# Top.net
KiCad netlist of a schematic drawn in Altium Designer
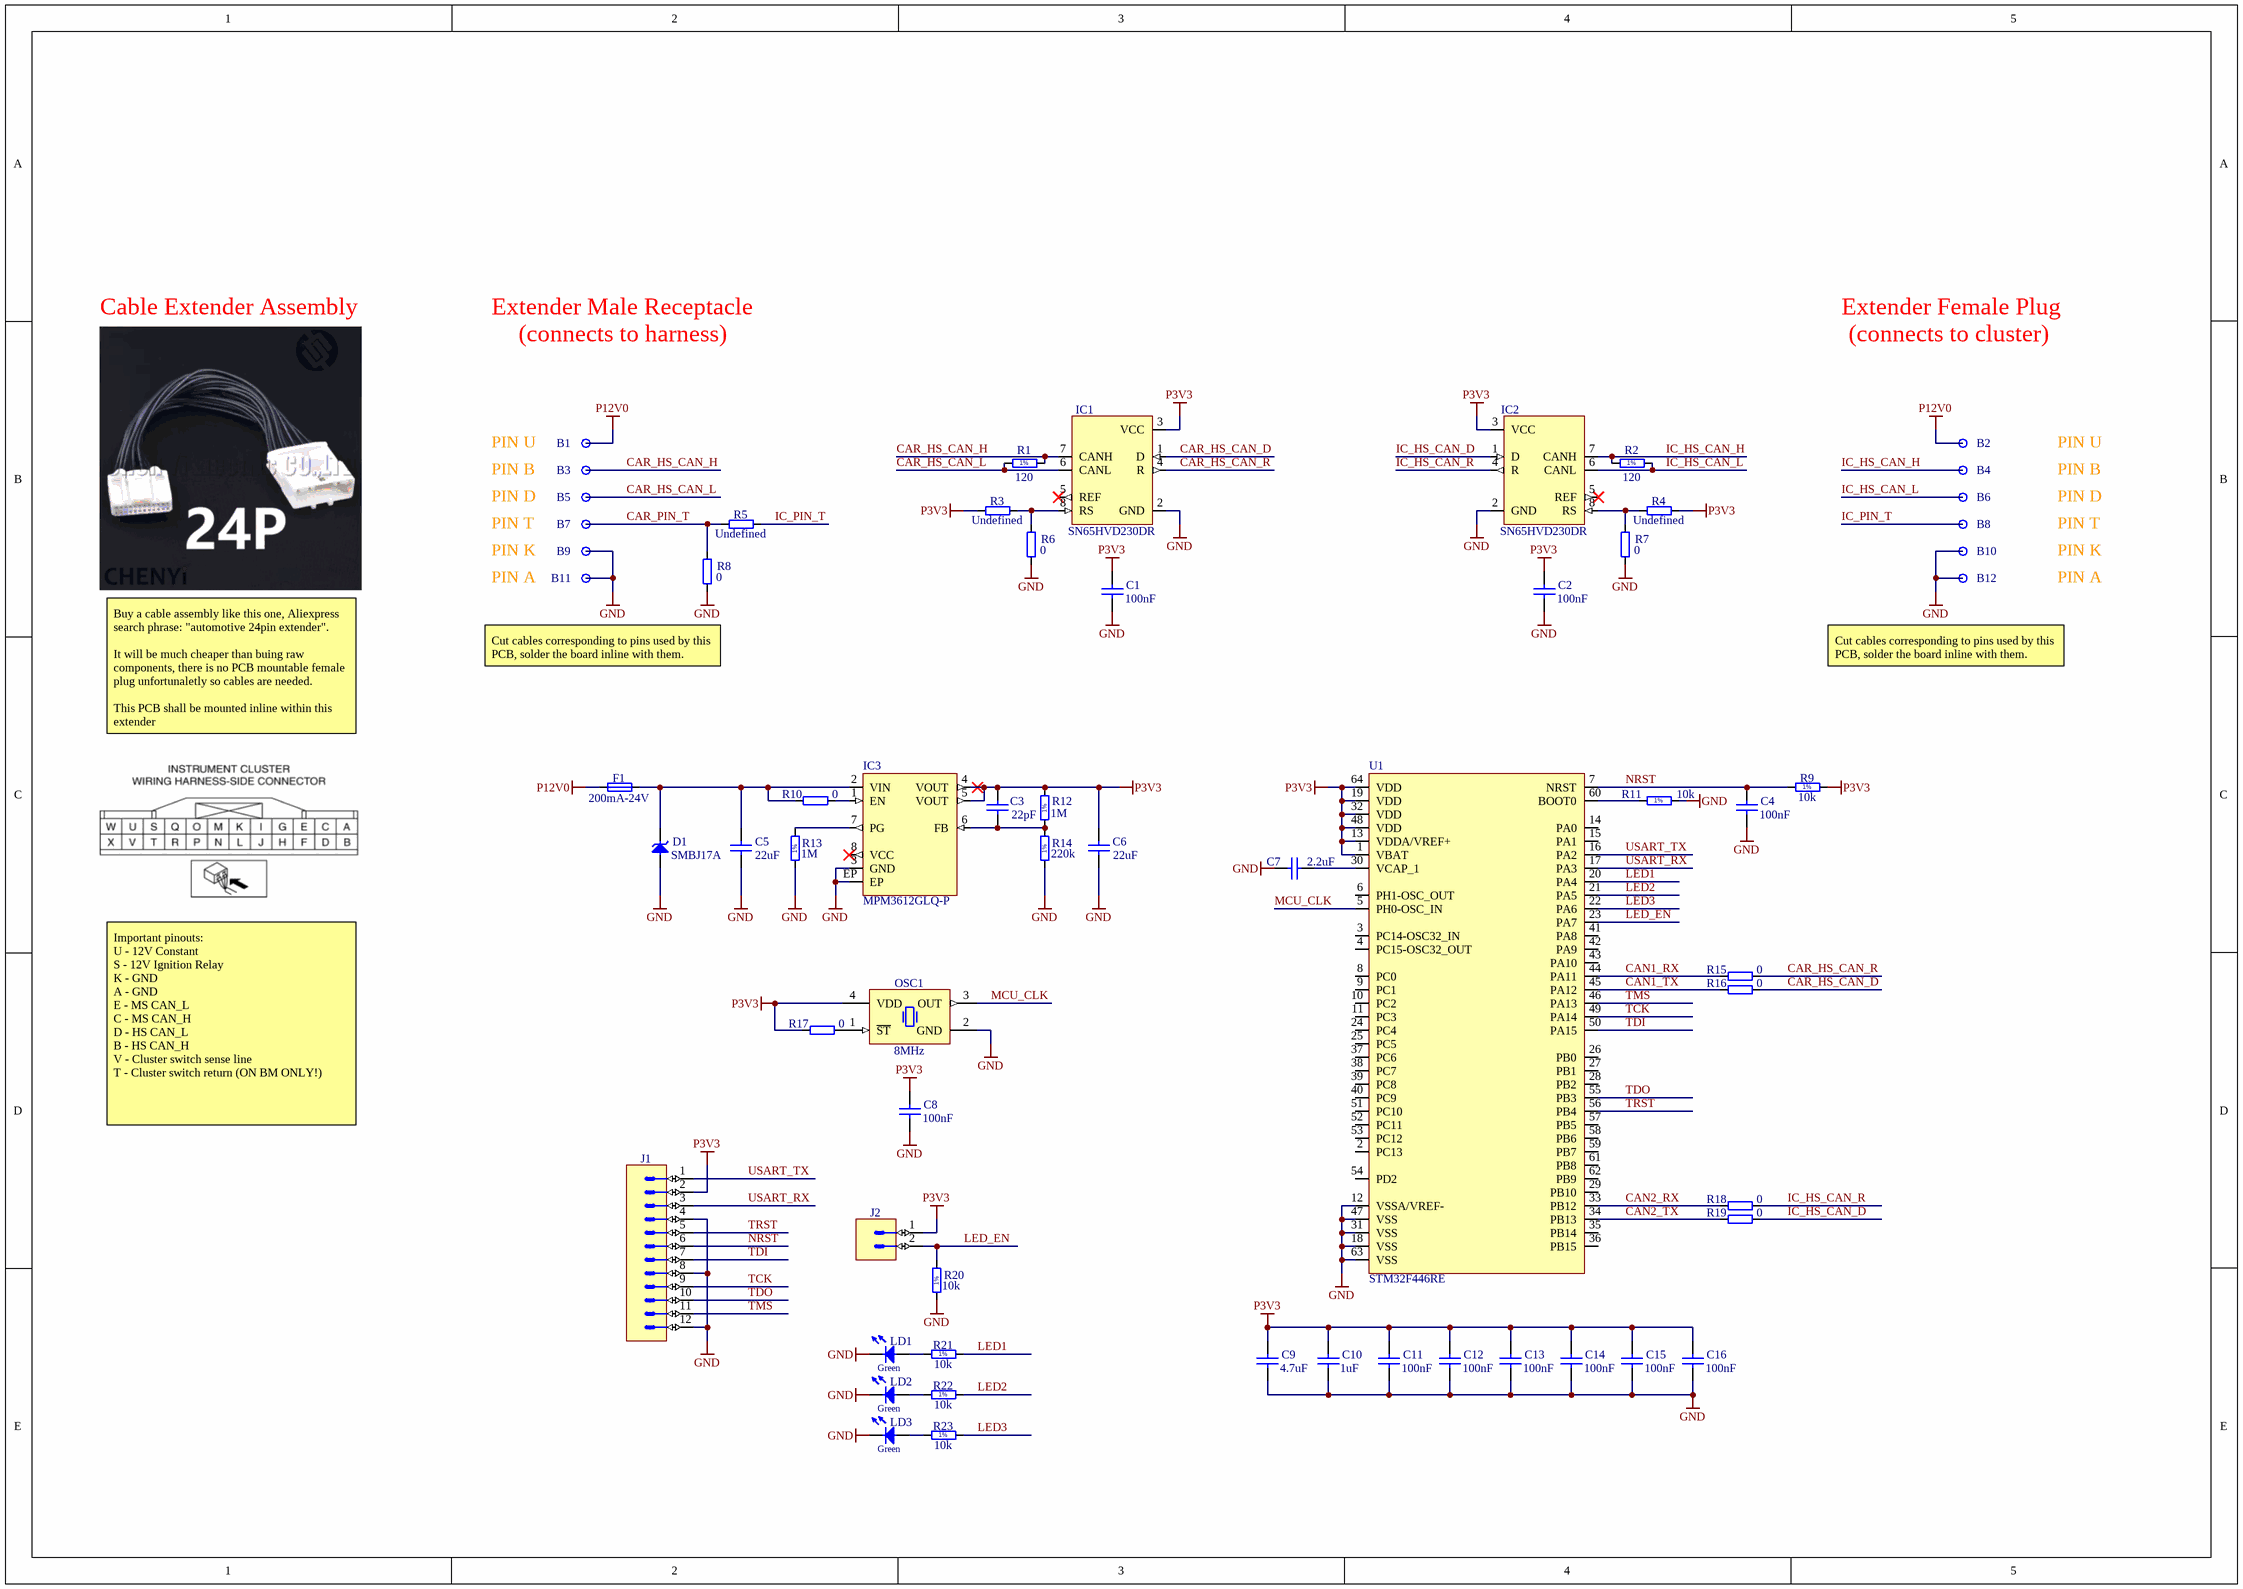
[diagram p0: Top.SchDoc]

(export (version "E")
  (design (tool "Eeschema 10.0.6"))
  (components
    (comp (ref "B1")
      (value "Plated Hole")
      (footprint "c170h100")
      (description "Single Terminal Socket")
      (fields (field (name "PART NUMBER") "PLATED_HOLE1.0_PAD1.7") (field (name "AUTHOR") "CERN DEM JLC"))
      (libsource (lib "Eletro-mechanical") (part "Single Terminal Socket"))
    )
    (comp (ref "B2")
      (value "Plated Hole")
      (footprint "c170h100")
      (description "Single Terminal Socket")
      (fields (field (name "PART NUMBER") "PLATED_HOLE1.0_PAD1.7") (field (name "AUTHOR") "CERN DEM JLC"))
      (libsource (lib "Eletro-mechanical") (part "Single Terminal Socket"))
    )
    (comp (ref "B3")
      (value "Plated Hole")
      (footprint "c170h100")
      (description "Single Terminal Socket")
      (fields (field (name "PART NUMBER") "PLATED_HOLE1.0_PAD1.7") (field (name "AUTHOR") "CERN DEM JLC"))
      (libsource (lib "Eletro-mechanical") (part "Single Terminal Socket"))
    )
    (comp (ref "B4")
      (value "Plated Hole")
      (footprint "c170h100")
      (description "Single Terminal Socket")
      (fields (field (name "PART NUMBER") "PLATED_HOLE1.0_PAD1.7") (field (name "AUTHOR") "CERN DEM JLC"))
      (libsource (lib "Eletro-mechanical") (part "Single Terminal Socket"))
    )
    (comp (ref "B5")
      (value "Plated Hole")
      (footprint "c170h100")
      (description "Single Terminal Socket")
      (fields (field (name "PART NUMBER") "PLATED_HOLE1.0_PAD1.7") (field (name "AUTHOR") "CERN DEM JLC"))
      (libsource (lib "Eletro-mechanical") (part "Single Terminal Socket"))
    )
    (comp (ref "B6")
      (value "Plated Hole")
      (footprint "c170h100")
      (description "Single Terminal Socket")
      (fields (field (name "PART NUMBER") "PLATED_HOLE1.0_PAD1.7") (field (name "AUTHOR") "CERN DEM JLC"))
      (libsource (lib "Eletro-mechanical") (part "Single Terminal Socket"))
    )
    (comp (ref "B7")
      (value "Plated Hole")
      (footprint "c170h100")
      (description "Single Terminal Socket")
      (fields (field (name "PART NUMBER") "PLATED_HOLE1.0_PAD1.7") (field (name "AUTHOR") "CERN DEM JLC"))
      (libsource (lib "Eletro-mechanical") (part "Single Terminal Socket"))
    )
    (comp (ref "B8")
      (value "Plated Hole")
      (footprint "c170h100")
      (description "Single Terminal Socket")
      (fields (field (name "PART NUMBER") "PLATED_HOLE1.0_PAD1.7") (field (name "AUTHOR") "CERN DEM JLC"))
      (libsource (lib "Eletro-mechanical") (part "Single Terminal Socket"))
    )
    (comp (ref "B9")
      (value "Plated Hole")
      (footprint "c170h100")
      (description "Single Terminal Socket")
      (fields (field (name "PART NUMBER") "PLATED_HOLE1.0_PAD1.7") (field (name "AUTHOR") "CERN DEM JLC"))
      (libsource (lib "Eletro-mechanical") (part "Single Terminal Socket"))
    )
    (comp (ref "B10")
      (value "Plated Hole")
      (footprint "c170h100")
      (description "Single Terminal Socket")
      (fields (field (name "PART NUMBER") "PLATED_HOLE1.0_PAD1.7") (field (name "AUTHOR") "CERN DEM JLC"))
      (libsource (lib "Eletro-mechanical") (part "Single Terminal Socket"))
    )
    (comp (ref "B11")
      (value "Plated Hole")
      (footprint "c170h100")
      (description "Single Terminal Socket")
      (fields (field (name "PART NUMBER") "PLATED_HOLE1.0_PAD1.7") (field (name "AUTHOR") "CERN DEM JLC"))
      (libsource (lib "Eletro-mechanical") (part "Single Terminal Socket"))
    )
    (comp (ref "B12")
      (value "Plated Hole")
      (footprint "c170h100")
      (description "Single Terminal Socket")
      (fields (field (name "PART NUMBER") "PLATED_HOLE1.0_PAD1.7") (field (name "AUTHOR") "CERN DEM JLC"))
      (libsource (lib "Eletro-mechanical") (part "Single Terminal Socket"))
    )
    (comp (ref "C1")
      (value "100nF")
      (footprint "CAPC1608X87N")
      (description "Non-polarised capacitor")
      (fields
        (field (name "PART NUMBER") "CC0603_100NF_50V_10%_X5R")
        (field (name "VOLTAGE") "50V")
        (field (name "AUTHOR") "CERN DEM MR")
      )
      (libsource (lib "Capacitors") (part "Capacitor - non polarized"))
    )
    (comp (ref "C2")
      (value "100nF")
      (footprint "CAPC1608X87N")
      (description "Non-polarised capacitor")
      (fields
        (field (name "PART NUMBER") "CC0603_100NF_50V_10%_X5R")
        (field (name "VOLTAGE") "50V")
        (field (name "AUTHOR") "CERN DEM MR")
      )
      (libsource (lib "Capacitors") (part "Capacitor - non polarized"))
    )
    (comp (ref "C3")
      (value "22pF")
      (footprint "CAPC1608X87N")
      (description "Non-polarised capacitor")
      (fields
        (field (name "PART NUMBER") "CC0603_22PF_50V_5%_NP0")
        (field (name "VOLTAGE") "50V")
        (field (name "AUTHOR") "CERN DEM JLC")
      )
      (libsource (lib "Capacitors") (part "Capacitor - non polarized"))
    )
    (comp (ref "C4")
      (value "100nF")
      (footprint "CAPC1608X87N")
      (description "Non-polarised capacitor")
      (fields
        (field (name "PART NUMBER") "CC0603_100NF_50V_10%_X5R")
        (field (name "VOLTAGE") "50V")
        (field (name "AUTHOR") "CERN DEM MR")
      )
      (libsource (lib "Capacitors") (part "Capacitor - non polarized"))
    )
    (comp (ref "C5")
      (value "22uF")
      (footprint "CAPC2012X135N")
      (description "Non-polarised capacitor")
      (fields
        (field (name "PART NUMBER") "CC0805_22UF_25V_20%_X6S")
        (field (name "VOLTAGE") "25V")
        (field (name "AUTHOR") "CERN DEM JLC")
      )
      (libsource (lib "Capacitors") (part "Capacitor - non polarized"))
    )
    (comp (ref "C6")
      (value "22uF")
      (footprint "CAPC2012X135N")
      (description "Non-polarised capacitor")
      (fields
        (field (name "PART NUMBER") "CC0805_22UF_25V_20%_X6S")
        (field (name "VOLTAGE") "25V")
        (field (name "AUTHOR") "CERN DEM JLC")
      )
      (libsource (lib "Capacitors") (part "Capacitor - non polarized"))
    )
    (comp (ref "C7")
      (value "2.2uF")
      (footprint "CAPC1608X90N")
      (description "Non-polarised capacitor")
      (fields
        (field (name "PART NUMBER") "CC0603_2.2UF_10V_20%_X7R")
        (field (name "VOLTAGE") "10V")
        (field (name "AUTHOR") "CERN DEM JLC")
      )
      (libsource (lib "Capacitors") (part "Capacitor - non polarized"))
    )
    (comp (ref "C8")
      (value "100nF")
      (footprint "CAPC1608X87N")
      (description "Non-polarised capacitor")
      (fields
        (field (name "PART NUMBER") "CC0603_100NF_50V_10%_X5R")
        (field (name "VOLTAGE") "50V")
        (field (name "AUTHOR") "CERN DEM MR")
      )
      (libsource (lib "Capacitors") (part "Capacitor - non polarized"))
    )
    (comp (ref "C9")
      (value "4.7uF")
      (footprint "CAPC1608X87N")
      (description "Non-polarised capacitor")
      (fields
        (field (name "PART NUMBER") "CC0603_4.7UF_6.3V_10%_X5R")
        (field (name "VOLTAGE") "6.3V")
        (field (name "AUTHOR") "CERN DEM JLC")
      )
      (libsource (lib "Capacitors") (part "Capacitor - non polarized"))
    )
    (comp (ref "C10")
      (value "1uF")
      (footprint "CAPC1608X87N")
      (description "Non-polarised capacitor")
      (fields
        (field (name "PART NUMBER") "CC0603_1UF_16V_10%_X7R")
        (field (name "VOLTAGE") "16V")
        (field (name "AUTHOR") "CERN DEM JLC")
      )
      (libsource (lib "Capacitors") (part "Capacitor - non polarized"))
    )
    (comp (ref "C11")
      (value "100nF")
      (footprint "CAPC1608X87N")
      (description "Non-polarised capacitor")
      (fields
        (field (name "PART NUMBER") "CC0603_100NF_50V_10%_X5R")
        (field (name "VOLTAGE") "50V")
        (field (name "AUTHOR") "CERN DEM MR")
      )
      (libsource (lib "Capacitors") (part "Capacitor - non polarized"))
    )
    (comp (ref "C12")
      (value "100nF")
      (footprint "CAPC1608X87N")
      (description "Non-polarised capacitor")
      (fields
        (field (name "PART NUMBER") "CC0603_100NF_50V_10%_X5R")
        (field (name "VOLTAGE") "50V")
        (field (name "AUTHOR") "CERN DEM MR")
      )
      (libsource (lib "Capacitors") (part "Capacitor - non polarized"))
    )
    (comp (ref "C13")
      (value "100nF")
      (footprint "CAPC1608X87N")
      (description "Non-polarised capacitor")
      (fields
        (field (name "PART NUMBER") "CC0603_100NF_50V_10%_X5R")
        (field (name "VOLTAGE") "50V")
        (field (name "AUTHOR") "CERN DEM MR")
      )
      (libsource (lib "Capacitors") (part "Capacitor - non polarized"))
    )
    (comp (ref "C14")
      (value "100nF")
      (footprint "CAPC1608X87N")
      (description "Non-polarised capacitor")
      (fields
        (field (name "PART NUMBER") "CC0603_100NF_50V_10%_X5R")
        (field (name "VOLTAGE") "50V")
        (field (name "AUTHOR") "CERN DEM MR")
      )
      (libsource (lib "Capacitors") (part "Capacitor - non polarized"))
    )
    (comp (ref "C15")
      (value "100nF")
      (footprint "CAPC1608X87N")
      (description "Non-polarised capacitor")
      (fields
        (field (name "PART NUMBER") "CC0603_100NF_50V_10%_X5R")
        (field (name "VOLTAGE") "50V")
        (field (name "AUTHOR") "CERN DEM MR")
      )
      (libsource (lib "Capacitors") (part "Capacitor - non polarized"))
    )
    (comp (ref "C16")
      (value "100nF")
      (footprint "CAPC1608X87N")
      (description "Non-polarised capacitor")
      (fields
        (field (name "PART NUMBER") "CC0603_100NF_50V_10%_X5R")
        (field (name "VOLTAGE") "50V")
        (field (name "AUTHOR") "CERN DEM MR")
      )
      (libsource (lib "Capacitors") (part "Capacitor - non polarized"))
    )
    (comp (ref "D1")
      (value "SMBJ17A")
      (footprint "DIOM5336X265N")
      (description "Zener Diode")
      (fields
        (field (name "VOLTAGE") "17V")
        (field (name "POWER") "600W")
        (field (name "AUTHOR") "CERN DEM JLC")
      )
      (libsource (lib "ICs And Semiconductors") (part "Diode Zener"))
    )
    (comp (ref "F1")
      (value "200mA-24V")
      (footprint "FUSR_LITTELFUSE_0805L010")
      (description "Fuse")
      (fields (field (name "PART NUMBER") "0805L020/24YR") (field (name "AUTHOR") "CERN DEM JLC"))
      (libsource (lib "Eletro-mechanical") (part "Fuse"))
    )
    (comp (ref "IC1")
      (value "SN65HVD230DR")
      (footprint "SOIC127P600X175-8N")
      (description "3.3V CAN Bus Transceiver")
      (fields (field (name "AUTHOR") "CERN DEM JMW"))
      (libsource (lib "Lib") (part "SN65HVD230DR"))
    )
    (comp (ref "IC2")
      (value "SN65HVD230DR")
      (footprint "SOIC127P600X175-8N")
      (description "3.3V CAN Bus Transceiver")
      (fields (field (name "AUTHOR") "CERN DEM JMW"))
      (libsource (lib "") (part "SN65HVD230DR_1"))
    )
    (comp (ref "IC3")
      (value "MPM3612GLQ-P")
      (footprint "LGA10")
      (libsource (lib "Lib") (part "MPM3612GLQ-P"))
    )
    (comp (ref "J1")
      (value "Header 12")
      (footprint "SAMTEC_TSW-106-23-L-D")
      (description "Connector 12 Male")
      (fields
        (field (name "PART NUMBER") "SAMTEC_TSW-106-23-L-D")
        (field (name "MANUFACTURER1 PART NUMBER") "TSW-106-23-L-D")
        (field (name "AUTHOR") "CERN DEM MR")
      )
      (libsource (lib "Connectors") (part "Connector 12 Male"))
    )
    (comp (ref "J2")
      (value "Header 2")
      (footprint "SAMTEC_TSW-101-23-L-D")
      (description "Connector 2 Male")
      (fields
        (field (name "PART NUMBER") "SAMTEC_TSW-101-23-L-D")
        (field (name "MANUFACTURER1 PART NUMBER") "TSW-101-23-L-D")
        (field (name "AUTHOR") "CERN DEM MR")
      )
      (libsource (lib "Connectors") (part "Connector 2 Male"))
    )
    (comp (ref "LD1")
      (value "Green")
      (footprint "LED_KINGBRIGHT_KPH-1608CGCK")
      (description "LED Green 1C 2A")
      (fields
        (field (name "PART NUMBER") "LED_KINGBRIGHT_KPH-1608CGCK")
        (field (name "MANUFACTURER1 PART NUMBER") "KPH-1608CGCK")
        (field (name "AUTHOR") "CERN DEM JLC")
      )
      (libsource (lib "ICs And Semiconductors") (part "LED Green 1C 2A"))
    )
    (comp (ref "LD2")
      (value "Green")
      (footprint "LED_KINGBRIGHT_KPH-1608CGCK")
      (description "LED Green 1C 2A")
      (fields
        (field (name "PART NUMBER") "LED_KINGBRIGHT_KPH-1608CGCK")
        (field (name "MANUFACTURER1 PART NUMBER") "KPH-1608CGCK")
        (field (name "AUTHOR") "CERN DEM JLC")
      )
      (libsource (lib "ICs And Semiconductors") (part "LED Green 1C 2A"))
    )
    (comp (ref "LD3")
      (value "Green")
      (footprint "LED_KINGBRIGHT_KPH-1608CGCK")
      (description "LED Green 1C 2A")
      (fields
        (field (name "PART NUMBER") "LED_KINGBRIGHT_KPH-1608CGCK")
        (field (name "MANUFACTURER1 PART NUMBER") "KPH-1608CGCK")
        (field (name "AUTHOR") "CERN DEM JLC")
      )
      (libsource (lib "ICs And Semiconductors") (part "LED Green 1C 2A"))
    )
    (comp (ref "OSC1")
      (value "8MHz")
      (footprint "OSC_MICROCHIP_CDFN2520-4LD-PL-1")
      (description "Oscillator 4 pins 1=S\\T\\ 2=GND 3=OUT 4=VDD")
      (fields
        (field (name "PART NUMBER") "OSC_8MHZ_MICROCHIP_DSC1003DL2-008.0000")
        (field (name "MANUFACTURER1 PART NUMBER") "DSC1003DL2-008.0000")
        (field (name "AUTHOR") "CERN DEM JLC")
      )
      (libsource (lib "ICs And Semiconductors") (part "Oscillator 1S{backslash}T{backslash} 2GND 3OUT 4VDD"))
    )
    (comp (ref "R1")
      (value "120")
      (footprint "RESC3216X65N")
      (description "Resistor - 1%")
      (fields
        (field (name "PART NUMBER") "R1206_120R_1%_0.25W_100PPM")
        (field (name "POWER") "0.25W")
        (field (name "AUTHOR") "CERN DEM JLC")
      )
      (libsource (lib "Resistors") (part "Resistor - 1%"))
    )
    (comp (ref "R2")
      (value "120")
      (footprint "RESC3216X65N")
      (description "Resistor - 1%")
      (fields
        (field (name "PART NUMBER") "R1206_120R_1%_0.25W_100PPM")
        (field (name "POWER") "0.25W")
        (field (name "AUTHOR") "CERN DEM JLC")
      )
      (libsource (lib "Resistors") (part "Resistor - 1%"))
    )
    (comp (ref "R3")
      (value "Undefined")
      (footprint "RESC1608X55N")
      (description "Resistor")
      (fields (field (name "PART NUMBER") "R0603_NO-VALUE") (field (name "AUTHOR") "CERN DEM JLC"))
      (libsource (lib "Resistors") (part "Resistor"))
    )
    (comp (ref "R4")
      (value "Undefined")
      (footprint "RESC1608X55N")
      (description "Resistor")
      (fields (field (name "PART NUMBER") "R0603_NO-VALUE") (field (name "AUTHOR") "CERN DEM JLC"))
      (libsource (lib "Resistors") (part "Resistor"))
    )
    (comp (ref "R5")
      (value "Undefined")
      (footprint "RESC1608X55N")
      (description "Resistor")
      (fields (field (name "PART NUMBER") "R0603_NO-VALUE") (field (name "AUTHOR") "CERN DEM JLC"))
      (libsource (lib "Resistors") (part "Resistor"))
    )
    (comp (ref "R6")
      (value "0")
      (footprint "RESC1608X55N")
      (description "Resistor")
      (fields
        (field (name "PART NUMBER") "R0603_0R_JUMPER")
        (field (name "MANUFACTURER") "GENERIC")
        (field (name "AUTHOR") "CERN DEM JLC")
      )
      (libsource (lib "Resistors") (part "Resistor"))
    )
    (comp (ref "R7")
      (value "0")
      (footprint "RESC1608X55N")
      (description "Resistor")
      (fields
        (field (name "PART NUMBER") "R0603_0R_JUMPER")
        (field (name "MANUFACTURER") "GENERIC")
        (field (name "AUTHOR") "CERN DEM JLC")
      )
      (libsource (lib "Resistors") (part "Resistor"))
    )
    (comp (ref "R8")
      (value "0")
      (footprint "RESC1608X55N")
      (description "Resistor")
      (fields
        (field (name "PART NUMBER") "R0603_0R_JUMPER")
        (field (name "MANUFACTURER") "GENERIC")
        (field (name "AUTHOR") "CERN DEM JLC")
      )
      (libsource (lib "Resistors") (part "Resistor"))
    )
    (comp (ref "R9")
      (value "10k")
      (footprint "RESC1608X55N")
      (description "Resistor - 1%")
      (fields
        (field (name "PART NUMBER") "R0603_10K_1%_0.1W_100PPM")
        (field (name "POWER") "0.1W")
        (field (name "AUTHOR") "CERN DEM JLC")
      )
      (libsource (lib "Resistors") (part "Resistor - 1%"))
    )
    (comp (ref "R10")
      (value "0")
      (footprint "RESC1608X55N")
      (description "Resistor")
      (fields
        (field (name "PART NUMBER") "R0603_0R_JUMPER")
        (field (name "MANUFACTURER") "GENERIC")
        (field (name "AUTHOR") "CERN DEM JLC")
      )
      (libsource (lib "Resistors") (part "Resistor"))
    )
    (comp (ref "R11")
      (value "10k")
      (footprint "RESC1608X55N")
      (description "Resistor - 1%")
      (fields
        (field (name "PART NUMBER") "R0603_10K_1%_0.1W_100PPM")
        (field (name "POWER") "0.1W")
        (field (name "AUTHOR") "CERN DEM JLC")
      )
      (libsource (lib "Resistors") (part "Resistor - 1%"))
    )
    (comp (ref "R12")
      (value "1M")
      (footprint "RESC1608X55N")
      (description "Resistor - 1%")
      (fields
        (field (name "PART NUMBER") "R0603_1M_1%_0.1W_100PPM")
        (field (name "POWER") "0.1W")
        (field (name "AUTHOR") "CERN DEM JLC")
      )
      (libsource (lib "Resistors") (part "Resistor - 1%"))
    )
    (comp (ref "R13")
      (value "1M")
      (footprint "RESC1608X55N")
      (description "Resistor - 1%")
      (fields
        (field (name "PART NUMBER") "R0603_1M_1%_0.1W_100PPM")
        (field (name "POWER") "0.1W")
        (field (name "AUTHOR") "CERN DEM JLC")
      )
      (libsource (lib "Resistors") (part "Resistor - 1%"))
    )
    (comp (ref "R14")
      (value "220k")
      (footprint "RESC1608X55N")
      (description "Resistor - 1%")
      (fields
        (field (name "PART NUMBER") "R0603_220K_1%_0.1W_100PPM")
        (field (name "POWER") "0.1W")
        (field (name "AUTHOR") "CERN DEM JLC")
      )
      (libsource (lib "Resistors") (part "Resistor - 1%"))
    )
    (comp (ref "R15")
      (value "0")
      (footprint "RESC1608X55N")
      (description "Resistor")
      (fields
        (field (name "PART NUMBER") "R0603_0R_JUMPER")
        (field (name "MANUFACTURER") "GENERIC")
        (field (name "AUTHOR") "CERN DEM JLC")
      )
      (libsource (lib "Resistors") (part "Resistor"))
    )
    (comp (ref "R16")
      (value "0")
      (footprint "RESC1608X55N")
      (description "Resistor")
      (fields
        (field (name "PART NUMBER") "R0603_0R_JUMPER")
        (field (name "MANUFACTURER") "GENERIC")
        (field (name "AUTHOR") "CERN DEM JLC")
      )
      (libsource (lib "Resistors") (part "Resistor"))
    )
    (comp (ref "R17")
      (value "0")
      (footprint "RESC1608X55N")
      (description "Resistor")
      (fields
        (field (name "PART NUMBER") "R0603_0R_JUMPER")
        (field (name "MANUFACTURER") "GENERIC")
        (field (name "AUTHOR") "CERN DEM JLC")
      )
      (libsource (lib "Resistors") (part "Resistor"))
    )
    (comp (ref "R18")
      (value "0")
      (footprint "RESC1608X55N")
      (description "Resistor")
      (fields
        (field (name "PART NUMBER") "R0603_0R_JUMPER")
        (field (name "MANUFACTURER") "GENERIC")
        (field (name "AUTHOR") "CERN DEM JLC")
      )
      (libsource (lib "Resistors") (part "Resistor"))
    )
    (comp (ref "R19")
      (value "0")
      (footprint "RESC1608X55N")
      (description "Resistor")
      (fields
        (field (name "PART NUMBER") "R0603_0R_JUMPER")
        (field (name "MANUFACTURER") "GENERIC")
        (field (name "AUTHOR") "CERN DEM JLC")
      )
      (libsource (lib "Resistors") (part "Resistor"))
    )
    (comp (ref "R20")
      (value "10k")
      (footprint "RESC1608X55N")
      (description "Resistor - 1%")
      (fields
        (field (name "PART NUMBER") "R0603_10K_1%_0.1W_100PPM")
        (field (name "POWER") "0.1W")
        (field (name "AUTHOR") "CERN DEM JLC")
      )
      (libsource (lib "Resistors") (part "Resistor - 1%"))
    )
    (comp (ref "R21")
      (value "10k")
      (footprint "RESC1608X55N")
      (description "Resistor - 1%")
      (fields
        (field (name "PART NUMBER") "R0603_10K_1%_0.1W_100PPM")
        (field (name "POWER") "0.1W")
        (field (name "AUTHOR") "CERN DEM JLC")
      )
      (libsource (lib "Resistors") (part "Resistor - 1%"))
    )
    (comp (ref "R22")
      (value "10k")
      (footprint "RESC1608X55N")
      (description "Resistor - 1%")
      (fields
        (field (name "PART NUMBER") "R0603_10K_1%_0.1W_100PPM")
        (field (name "POWER") "0.1W")
        (field (name "AUTHOR") "CERN DEM JLC")
      )
      (libsource (lib "Resistors") (part "Resistor - 1%"))
    )
    (comp (ref "R23")
      (value "10k")
      (footprint "RESC1608X55N")
      (description "Resistor - 1%")
      (fields
        (field (name "PART NUMBER") "R0603_10K_1%_0.1W_100PPM")
        (field (name "POWER") "0.1W")
        (field (name "AUTHOR") "CERN DEM JLC")
      )
      (libsource (lib "Resistors") (part "Resistor - 1%"))
    )
    (comp (ref "U1")
      (value "STM32F446RE")
      (footprint "STM-LQFP64_N")
      (description "Arm® Cortex®-M4 core with DSP and FPU, 512 Kbytes Flash, 180 MHz CPU, ART Accelerator, Dual QSPI")
      (fields (field (name "MANUFACTURER1 PART NUMBER") "STM32F446RET7") (field (name "AUTHOR") "PC"))
      (libsource (lib "ICs And Semiconductors") (part "STM32F446RE"))
    )
  )
  (nets
    (net (code "1") (name "/CAN1_RX") (class "Default")
      (node (ref "R15") (pin "2") (pinfunction "2_2") (pintype "passive"))
      (node (ref "U1") (pin "44") (pinfunction "PA11_44") (pintype "passive"))
    )
    (net (code "2") (name "/CAN1_TX") (class "Default")
      (node (ref "R16") (pin "2") (pinfunction "2_2") (pintype "passive"))
      (node (ref "U1") (pin "45") (pinfunction "PA12_45") (pintype "passive"))
    )
    (net (code "3") (name "/CAN2_RX") (class "Default")
      (node (ref "R18") (pin "2") (pinfunction "2_2") (pintype "passive"))
      (node (ref "U1") (pin "33") (pinfunction "PB12_33") (pintype "passive"))
    )
    (net (code "4") (name "/CAN2_TX") (class "Default")
      (node (ref "R19") (pin "2") (pinfunction "2_2") (pintype "passive"))
      (node (ref "U1") (pin "34") (pinfunction "PB13_34") (pintype "passive"))
    )
    (net (code "5") (name "/CAR_HS_CAN_D") (class "Default")
      (node (ref "IC1") (pin "1") (pinfunction "D_1") (pintype "input"))
      (node (ref "R16") (pin "1") (pinfunction "1_1") (pintype "passive"))
    )
    (net (code "6") (name "/CAR_HS_CAN_H") (class "Default")
      (node (ref "B3") (pin "1") (pinfunction "1_1") (pintype "bidirectional"))
      (node (ref "IC1") (pin "7") (pinfunction "CANH_7") (pintype "bidirectional"))
      (node (ref "R1") (pin "1") (pinfunction "1_1") (pintype "passive"))
    )
    (net (code "7") (name "/CAR_HS_CAN_L") (class "Default")
      (node (ref "B5") (pin "1") (pinfunction "1_1") (pintype "bidirectional"))
      (node (ref "IC1") (pin "6") (pinfunction "CANL_6") (pintype "bidirectional"))
      (node (ref "R1") (pin "2") (pinfunction "2_2") (pintype "passive"))
    )
    (net (code "8") (name "/CAR_HS_CAN_R") (class "Default")
      (node (ref "IC1") (pin "4") (pinfunction "R_4") (pintype "output"))
      (node (ref "R15") (pin "1") (pinfunction "1_1") (pintype "passive"))
    )
    (net (code "9") (name "/CAR_PIN_T") (class "Default")
      (node (ref "B7") (pin "1") (pinfunction "1_1") (pintype "bidirectional"))
      (node (ref "R5") (pin "1") (pinfunction "1_1") (pintype "passive"))
      (node (ref "R8") (pin "2") (pinfunction "2_2") (pintype "passive"))
    )
    (net (code "10") (name "/IC_HS_CAN_D") (class "Default")
      (node (ref "IC2") (pin "1") (pinfunction "D_1") (pintype "input"))
      (node (ref "R19") (pin "1") (pinfunction "1_1") (pintype "passive"))
    )
    (net (code "11") (name "/IC_HS_CAN_H") (class "Default")
      (node (ref "B4") (pin "1") (pinfunction "1_1") (pintype "bidirectional"))
      (node (ref "IC2") (pin "7") (pinfunction "CANH_7") (pintype "bidirectional"))
      (node (ref "R2") (pin "1") (pinfunction "1_1") (pintype "passive"))
    )
    (net (code "12") (name "/IC_HS_CAN_L") (class "Default")
      (node (ref "B6") (pin "1") (pinfunction "1_1") (pintype "bidirectional"))
      (node (ref "IC2") (pin "6") (pinfunction "CANL_6") (pintype "bidirectional"))
      (node (ref "R2") (pin "2") (pinfunction "2_2") (pintype "passive"))
    )
    (net (code "13") (name "/IC_HS_CAN_R") (class "Default")
      (node (ref "IC2") (pin "4") (pinfunction "R_4") (pintype "output"))
      (node (ref "R18") (pin "1") (pinfunction "1_1") (pintype "passive"))
    )
    (net (code "14") (name "/IC_PIN_T") (class "Default")
      (node (ref "B8") (pin "1") (pinfunction "1_1") (pintype "bidirectional"))
      (node (ref "R5") (pin "2") (pinfunction "2_2") (pintype "passive"))
    )
    (net (code "15") (name "/LED1") (class "Default")
      (node (ref "R21") (pin "2") (pinfunction "2_2") (pintype "passive"))
      (node (ref "U1") (pin "20") (pinfunction "PA4_20") (pintype "passive"))
    )
    (net (code "16") (name "/LED2") (class "Default")
      (node (ref "R22") (pin "2") (pinfunction "2_2") (pintype "passive"))
      (node (ref "U1") (pin "21") (pinfunction "PA5_21") (pintype "passive"))
    )
    (net (code "17") (name "/LED3") (class "Default")
      (node (ref "R23") (pin "2") (pinfunction "2_2") (pintype "passive"))
      (node (ref "U1") (pin "22") (pinfunction "PA6_22") (pintype "passive"))
    )
    (net (code "18") (name "/LED_EN") (class "Default")
      (node (ref "J2") (pin "2") (pinfunction "2_2") (pintype "bidirectional"))
      (node (ref "R20") (pin "2") (pinfunction "2_2") (pintype "passive"))
      (node (ref "U1") (pin "23") (pinfunction "PA7_23") (pintype "passive"))
    )
    (net (code "19") (name "/MCU_CLK") (class "Default")
      (node (ref "OSC1") (pin "3") (pinfunction "OUT_3") (pintype "output"))
      (node (ref "U1") (pin "5") (pinfunction "PH0-OSC_IN_5") (pintype "passive"))
    )
    (net (code "20") (name "/NRST") (class "Default")
      (node (ref "C4") (pin "2") (pinfunction "2_2") (pintype "passive"))
      (node (ref "J1") (pin "6") (pinfunction "6_6") (pintype "bidirectional"))
      (node (ref "R9") (pin "1") (pinfunction "1_1") (pintype "passive"))
      (node (ref "U1") (pin "7") (pinfunction "NRST_7") (pintype "passive"))
    )
    (net (code "21") (name "/TCK") (class "Default")
      (node (ref "J1") (pin "9") (pinfunction "9_9") (pintype "bidirectional"))
      (node (ref "U1") (pin "49") (pinfunction "PA14_49") (pintype "passive"))
    )
    (net (code "22") (name "/TDI") (class "Default")
      (node (ref "J1") (pin "7") (pinfunction "7_7") (pintype "bidirectional"))
      (node (ref "U1") (pin "50") (pinfunction "PA15_50") (pintype "passive"))
    )
    (net (code "23") (name "/TDO") (class "Default")
      (node (ref "J1") (pin "10") (pinfunction "10_10") (pintype "bidirectional"))
      (node (ref "U1") (pin "55") (pinfunction "PB3_55") (pintype "passive"))
    )
    (net (code "24") (name "/TMS") (class "Default")
      (node (ref "J1") (pin "11") (pinfunction "11_11") (pintype "bidirectional"))
      (node (ref "U1") (pin "46") (pinfunction "PA13_46") (pintype "passive"))
    )
    (net (code "25") (name "/TRST") (class "Default")
      (node (ref "J1") (pin "5") (pinfunction "5_5") (pintype "bidirectional"))
      (node (ref "U1") (pin "56") (pinfunction "PB4_56") (pintype "passive"))
    )
    (net (code "26") (name "/USART_RX") (class "Default")
      (node (ref "J1") (pin "3") (pinfunction "3_3") (pintype "bidirectional"))
      (node (ref "U1") (pin "17") (pinfunction "PA3_17") (pintype "passive"))
    )
    (net (code "27") (name "/USART_TX") (class "Default")
      (node (ref "J1") (pin "1") (pinfunction "1_1") (pintype "bidirectional"))
      (node (ref "U1") (pin "16") (pinfunction "PA2_16") (pintype "passive"))
    )
    (net (code "28") (name "GND") (class "Default")
      (node (ref "B10") (pin "1") (pinfunction "1_1") (pintype "bidirectional"))
      (node (ref "B11") (pin "1") (pinfunction "1_1") (pintype "bidirectional"))
      (node (ref "B12") (pin "1") (pinfunction "1_1") (pintype "bidirectional"))
      (node (ref "B9") (pin "1") (pinfunction "1_1") (pintype "bidirectional"))
      (node (ref "C1") (pin "1") (pinfunction "1_1") (pintype "passive"))
      (node (ref "C10") (pin "1") (pinfunction "1_1") (pintype "passive"))
      (node (ref "C11") (pin "1") (pinfunction "1_1") (pintype "passive"))
      (node (ref "C12") (pin "1") (pinfunction "1_1") (pintype "passive"))
      (node (ref "C13") (pin "1") (pinfunction "1_1") (pintype "passive"))
      (node (ref "C14") (pin "1") (pinfunction "1_1") (pintype "passive"))
      (node (ref "C15") (pin "1") (pinfunction "1_1") (pintype "passive"))
      (node (ref "C16") (pin "1") (pinfunction "1_1") (pintype "passive"))
      (node (ref "C2") (pin "1") (pinfunction "1_1") (pintype "passive"))
      (node (ref "C4") (pin "1") (pinfunction "1_1") (pintype "passive"))
      (node (ref "C5") (pin "1") (pinfunction "1_1") (pintype "passive"))
      (node (ref "C6") (pin "1") (pinfunction "1_1") (pintype "passive"))
      (node (ref "C7") (pin "1") (pinfunction "1_1") (pintype "passive"))
      (node (ref "C8") (pin "1") (pinfunction "1_1") (pintype "passive"))
      (node (ref "C9") (pin "1") (pinfunction "1_1") (pintype "passive"))
      (node (ref "D1") (pin "2") (pinfunction "A_2") (pintype "passive"))
      (node (ref "IC1") (pin "2") (pinfunction "GND_2") (pintype "power_in"))
      (node (ref "IC2") (pin "2") (pinfunction "GND_2") (pintype "power_in"))
      (node (ref "IC3") (pin "3") (pinfunction "GND_3") (pintype "power_in"))
      (node (ref "IC3") (pin "EP") (pinfunction "EP_EP") (pintype "power_in"))
      (node (ref "J1") (pin "12") (pinfunction "12_12") (pintype "bidirectional"))
      (node (ref "J1") (pin "4") (pinfunction "4_4") (pintype "bidirectional"))
      (node (ref "J1") (pin "8") (pinfunction "8_8") (pintype "bidirectional"))
      (node (ref "LD1") (pin "1") (pinfunction "C_1") (pintype "passive"))
      (node (ref "LD2") (pin "1") (pinfunction "C_1") (pintype "passive"))
      (node (ref "LD3") (pin "1") (pinfunction "C_1") (pintype "passive"))
      (node (ref "OSC1") (pin "2") (pinfunction "GND_2") (pintype "power_in"))
      (node (ref "R11") (pin "2") (pinfunction "2_2") (pintype "passive"))
      (node (ref "R13") (pin "1") (pinfunction "1_1") (pintype "passive"))
      (node (ref "R14") (pin "1") (pinfunction "1_1") (pintype "passive"))
      (node (ref "R20") (pin "1") (pinfunction "1_1") (pintype "passive"))
      (node (ref "R6") (pin "1") (pinfunction "1_1") (pintype "passive"))
      (node (ref "R7") (pin "1") (pinfunction "1_1") (pintype "passive"))
      (node (ref "R8") (pin "1") (pinfunction "1_1") (pintype "passive"))
      (node (ref "U1") (pin "12") (pinfunction "VSSA/VREF-_12") (pintype "passive"))
      (node (ref "U1") (pin "18") (pinfunction "VSS_18") (pintype "passive"))
      (node (ref "U1") (pin "31") (pinfunction "VSS_31") (pintype "passive"))
      (node (ref "U1") (pin "47") (pinfunction "VSS_47") (pintype "passive"))
      (node (ref "U1") (pin "63") (pinfunction "VSS_63") (pintype "passive"))
    )
    (net (code "29") (name "Net-(D1-C)") (class "Default")
      (node (ref "C5") (pin "2") (pinfunction "2_2") (pintype "passive"))
      (node (ref "D1") (pin "1") (pinfunction "C_1") (pintype "passive"))
      (node (ref "F1") (pin "2") (pinfunction "2_2") (pintype "passive"))
      (node (ref "IC3") (pin "2") (pinfunction "VIN_2") (pintype "power_in"))
      (node (ref "R10") (pin "2") (pinfunction "2_2") (pintype "passive"))
    )
    (net (code "30") (name "Net-(IC1-RS)") (class "Default")
      (node (ref "IC1") (pin "8") (pinfunction "RS_8") (pintype "input"))
      (node (ref "R3") (pin "1") (pinfunction "1_1") (pintype "passive"))
      (node (ref "R6") (pin "2") (pinfunction "2_2") (pintype "passive"))
    )
    (net (code "31") (name "Net-(IC2-RS)") (class "Default")
      (node (ref "IC2") (pin "8") (pinfunction "RS_8") (pintype "input"))
      (node (ref "R4") (pin "1") (pinfunction "1_1") (pintype "passive"))
      (node (ref "R7") (pin "2") (pinfunction "2_2") (pintype "passive"))
    )
    (net (code "32") (name "Net-(IC3-EN)") (class "Default")
      (node (ref "IC3") (pin "1") (pinfunction "EN_1") (pintype "input"))
      (node (ref "R10") (pin "1") (pinfunction "1_1") (pintype "passive"))
    )
    (net (code "33") (name "Net-(IC3-FB)") (class "Default")
      (node (ref "C3") (pin "1") (pinfunction "1_1") (pintype "passive"))
      (node (ref "IC3") (pin "6") (pinfunction "FB_6") (pintype "input"))
      (node (ref "R12") (pin "1") (pinfunction "1_1") (pintype "passive"))
      (node (ref "R14") (pin "2") (pinfunction "2_2") (pintype "passive"))
    )
    (net (code "34") (name "Net-(IC3-PG)") (class "Default")
      (node (ref "IC3") (pin "7") (pinfunction "PG_7") (pintype "output"))
      (node (ref "R13") (pin "2") (pinfunction "2_2") (pintype "passive"))
    )
    (net (code "35") (name "Net-(LD1-A)") (class "Default")
      (node (ref "LD1") (pin "2") (pinfunction "A_2") (pintype "passive"))
      (node (ref "R21") (pin "1") (pinfunction "1_1") (pintype "passive"))
    )
    (net (code "36") (name "Net-(LD2-A)") (class "Default")
      (node (ref "LD2") (pin "2") (pinfunction "A_2") (pintype "passive"))
      (node (ref "R22") (pin "1") (pinfunction "1_1") (pintype "passive"))
    )
    (net (code "37") (name "Net-(LD3-A)") (class "Default")
      (node (ref "LD3") (pin "2") (pinfunction "A_2") (pintype "passive"))
      (node (ref "R23") (pin "1") (pinfunction "1_1") (pintype "passive"))
    )
    (net (code "38") (name "Net-(OSC1-~{ST})") (class "Default")
      (node (ref "OSC1") (pin "1") (pinfunction "~{ST}_1") (pintype "input"))
      (node (ref "R17") (pin "1") (pinfunction "1_1") (pintype "passive"))
    )
    (net (code "39") (name "Net-(U1-BOOT0)") (class "Default")
      (node (ref "R11") (pin "1") (pinfunction "1_1") (pintype "passive"))
      (node (ref "U1") (pin "60") (pinfunction "BOOT0_60") (pintype "passive"))
    )
    (net (code "40") (name "Net-(U1-VCAP_1)") (class "Default")
      (node (ref "C7") (pin "2") (pinfunction "2_2") (pintype "passive"))
      (node (ref "U1") (pin "30") (pinfunction "VCAP_1_30") (pintype "passive"))
    )
    (net (code "41") (name "P3V3") (class "Default")
      (node (ref "C1") (pin "2") (pinfunction "2_2") (pintype "passive"))
      (node (ref "C10") (pin "2") (pinfunction "2_2") (pintype "passive"))
      (node (ref "C11") (pin "2") (pinfunction "2_2") (pintype "passive"))
      (node (ref "C12") (pin "2") (pinfunction "2_2") (pintype "passive"))
      (node (ref "C13") (pin "2") (pinfunction "2_2") (pintype "passive"))
      (node (ref "C14") (pin "2") (pinfunction "2_2") (pintype "passive"))
      (node (ref "C15") (pin "2") (pinfunction "2_2") (pintype "passive"))
      (node (ref "C16") (pin "2") (pinfunction "2_2") (pintype "passive"))
      (node (ref "C2") (pin "2") (pinfunction "2_2") (pintype "passive"))
      (node (ref "C3") (pin "2") (pinfunction "2_2") (pintype "passive"))
      (node (ref "C6") (pin "2") (pinfunction "2_2") (pintype "passive"))
      (node (ref "C8") (pin "2") (pinfunction "2_2") (pintype "passive"))
      (node (ref "C9") (pin "2") (pinfunction "2_2") (pintype "passive"))
      (node (ref "IC1") (pin "3") (pinfunction "VCC_3") (pintype "power_in"))
      (node (ref "IC2") (pin "3") (pinfunction "VCC_3") (pintype "power_in"))
      (node (ref "IC3") (pin "4") (pinfunction "VOUT_4") (pintype "output"))
      (node (ref "IC3") (pin "5") (pinfunction "VOUT_5") (pintype "output"))
      (node (ref "J1") (pin "2") (pinfunction "2_2") (pintype "bidirectional"))
      (node (ref "J2") (pin "1") (pinfunction "1_1") (pintype "bidirectional"))
      (node (ref "OSC1") (pin "4") (pinfunction "VDD_4") (pintype "power_in"))
      (node (ref "R12") (pin "2") (pinfunction "2_2") (pintype "passive"))
      (node (ref "R17") (pin "2") (pinfunction "2_2") (pintype "passive"))
      (node (ref "R3") (pin "2") (pinfunction "2_2") (pintype "passive"))
      (node (ref "R4") (pin "2") (pinfunction "2_2") (pintype "passive"))
      (node (ref "R9") (pin "2") (pinfunction "2_2") (pintype "passive"))
      (node (ref "U1") (pin "1") (pinfunction "VBAT_1") (pintype "passive"))
      (node (ref "U1") (pin "13") (pinfunction "VDDA/VREF+_13") (pintype "passive"))
      (node (ref "U1") (pin "19") (pinfunction "VDD_19") (pintype "passive"))
      (node (ref "U1") (pin "32") (pinfunction "VDD_32") (pintype "passive"))
      (node (ref "U1") (pin "48") (pinfunction "VDD_48") (pintype "passive"))
      (node (ref "U1") (pin "64") (pinfunction "VDD_64") (pintype "passive"))
    )
    (net (code "42") (name "P12V0") (class "Default")
      (node (ref "B1") (pin "1") (pinfunction "1_1") (pintype "bidirectional"))
      (node (ref "B2") (pin "1") (pinfunction "1_1") (pintype "bidirectional"))
      (node (ref "F1") (pin "1") (pinfunction "1_1") (pintype "passive"))
    )
    (net (code "43") (name "unconnected-(IC1-REF-Pad5)") (class "Default")
      (node (ref "IC1") (pin "5") (pinfunction "REF_5") (pintype "output+no_connect"))
    )
    (net (code "44") (name "unconnected-(IC2-REF-Pad5)") (class "Default")
      (node (ref "IC2") (pin "5") (pinfunction "REF_5") (pintype "output+no_connect"))
    )
    (net (code "45") (name "unconnected-(IC3-VCC-Pad8)") (class "Default")
      (node (ref "IC3") (pin "8") (pinfunction "VCC_8") (pintype "output+no_connect"))
    )
    (net (code "46") (name "unconnected-(U1-PA0-Pad14)") (class "Default")
      (node (ref "U1") (pin "14") (pinfunction "PA0_14") (pintype "passive"))
    )
    (net (code "47") (name "unconnected-(U1-PA1-Pad15)") (class "Default")
      (node (ref "U1") (pin "15") (pinfunction "PA1_15") (pintype "passive"))
    )
    (net (code "48") (name "unconnected-(U1-PA8-Pad41)") (class "Default")
      (node (ref "U1") (pin "41") (pinfunction "PA8_41") (pintype "passive"))
    )
    (net (code "49") (name "unconnected-(U1-PA9-Pad42)") (class "Default")
      (node (ref "U1") (pin "42") (pinfunction "PA9_42") (pintype "passive"))
    )
    (net (code "50") (name "unconnected-(U1-PA10-Pad43)") (class "Default")
      (node (ref "U1") (pin "43") (pinfunction "PA10_43") (pintype "passive"))
    )
    (net (code "51") (name "unconnected-(U1-PB0-Pad26)") (class "Default")
      (node (ref "U1") (pin "26") (pinfunction "PB0_26") (pintype "passive"))
    )
    (net (code "52") (name "unconnected-(U1-PB1-Pad27)") (class "Default")
      (node (ref "U1") (pin "27") (pinfunction "PB1_27") (pintype "passive"))
    )
    (net (code "53") (name "unconnected-(U1-PB2-Pad28)") (class "Default")
      (node (ref "U1") (pin "28") (pinfunction "PB2_28") (pintype "passive"))
    )
    (net (code "54") (name "unconnected-(U1-PB5-Pad57)") (class "Default")
      (node (ref "U1") (pin "57") (pinfunction "PB5_57") (pintype "passive"))
    )
    (net (code "55") (name "unconnected-(U1-PB6-Pad58)") (class "Default")
      (node (ref "U1") (pin "58") (pinfunction "PB6_58") (pintype "passive"))
    )
    (net (code "56") (name "unconnected-(U1-PB7-Pad59)") (class "Default")
      (node (ref "U1") (pin "59") (pinfunction "PB7_59") (pintype "passive"))
    )
    (net (code "57") (name "unconnected-(U1-PB8-Pad61)") (class "Default")
      (node (ref "U1") (pin "61") (pinfunction "PB8_61") (pintype "passive"))
    )
    (net (code "58") (name "unconnected-(U1-PB9-Pad62)") (class "Default")
      (node (ref "U1") (pin "62") (pinfunction "PB9_62") (pintype "passive"))
    )
    (net (code "59") (name "unconnected-(U1-PB10-Pad29)") (class "Default")
      (node (ref "U1") (pin "29") (pinfunction "PB10_29") (pintype "passive"))
    )
    (net (code "60") (name "unconnected-(U1-PB14-Pad35)") (class "Default")
      (node (ref "U1") (pin "35") (pinfunction "PB14_35") (pintype "passive"))
    )
    (net (code "61") (name "unconnected-(U1-PB15-Pad36)") (class "Default")
      (node (ref "U1") (pin "36") (pinfunction "PB15_36") (pintype "passive"))
    )
    (net (code "62") (name "unconnected-(U1-PC0-Pad8)") (class "Default")
      (node (ref "U1") (pin "8") (pinfunction "PC0_8") (pintype "passive"))
    )
    (net (code "63") (name "unconnected-(U1-PC1-Pad9)") (class "Default")
      (node (ref "U1") (pin "9") (pinfunction "PC1_9") (pintype "passive"))
    )
    (net (code "64") (name "unconnected-(U1-PC2-Pad10)") (class "Default")
      (node (ref "U1") (pin "10") (pinfunction "PC2_10") (pintype "passive"))
    )
    (net (code "65") (name "unconnected-(U1-PC3-Pad11)") (class "Default")
      (node (ref "U1") (pin "11") (pinfunction "PC3_11") (pintype "passive"))
    )
    (net (code "66") (name "unconnected-(U1-PC4-Pad24)") (class "Default")
      (node (ref "U1") (pin "24") (pinfunction "PC4_24") (pintype "passive"))
    )
    (net (code "67") (name "unconnected-(U1-PC5-Pad25)") (class "Default")
      (node (ref "U1") (pin "25") (pinfunction "PC5_25") (pintype "passive"))
    )
    (net (code "68") (name "unconnected-(U1-PC6-Pad37)") (class "Default")
      (node (ref "U1") (pin "37") (pinfunction "PC6_37") (pintype "passive"))
    )
    (net (code "69") (name "unconnected-(U1-PC7-Pad38)") (class "Default")
      (node (ref "U1") (pin "38") (pinfunction "PC7_38") (pintype "passive"))
    )
    (net (code "70") (name "unconnected-(U1-PC8-Pad39)") (class "Default")
      (node (ref "U1") (pin "39") (pinfunction "PC8_39") (pintype "passive"))
    )
    (net (code "71") (name "unconnected-(U1-PC9-Pad40)") (class "Default")
      (node (ref "U1") (pin "40") (pinfunction "PC9_40") (pintype "passive"))
    )
    (net (code "72") (name "unconnected-(U1-PC10-Pad51)") (class "Default")
      (node (ref "U1") (pin "51") (pinfunction "PC10_51") (pintype "passive"))
    )
    (net (code "73") (name "unconnected-(U1-PC11-Pad52)") (class "Default")
      (node (ref "U1") (pin "52") (pinfunction "PC11_52") (pintype "passive"))
    )
    (net (code "74") (name "unconnected-(U1-PC12-Pad53)") (class "Default")
      (node (ref "U1") (pin "53") (pinfunction "PC12_53") (pintype "passive"))
    )
    (net (code "75") (name "unconnected-(U1-PC13-Pad2)") (class "Default")
      (node (ref "U1") (pin "2") (pinfunction "PC13_2") (pintype "passive"))
    )
    (net (code "76") (name "unconnected-(U1-PC14-OSC32_IN-Pad3)") (class "Default")
      (node (ref "U1") (pin "3") (pinfunction "PC14-OSC32_IN_3") (pintype "passive"))
    )
    (net (code "77") (name "unconnected-(U1-PC15-OSC32_OUT-Pad4)") (class "Default")
      (node (ref "U1") (pin "4") (pinfunction "PC15-OSC32_OUT_4") (pintype "passive"))
    )
    (net (code "78") (name "unconnected-(U1-PD2-Pad54)") (class "Default")
      (node (ref "U1") (pin "54") (pinfunction "PD2_54") (pintype "passive"))
    )
    (net (code "79") (name "unconnected-(U1-PH1-OSC_OUT-Pad6)") (class "Default")
      (node (ref "U1") (pin "6") (pinfunction "PH1-OSC_OUT_6") (pintype "passive"))
    )
  )
)
